# Jade_v1_schematics_PG2_ESP32_SUBSYS.net
KiCad netlist of a schematic drawn in Altium Designer
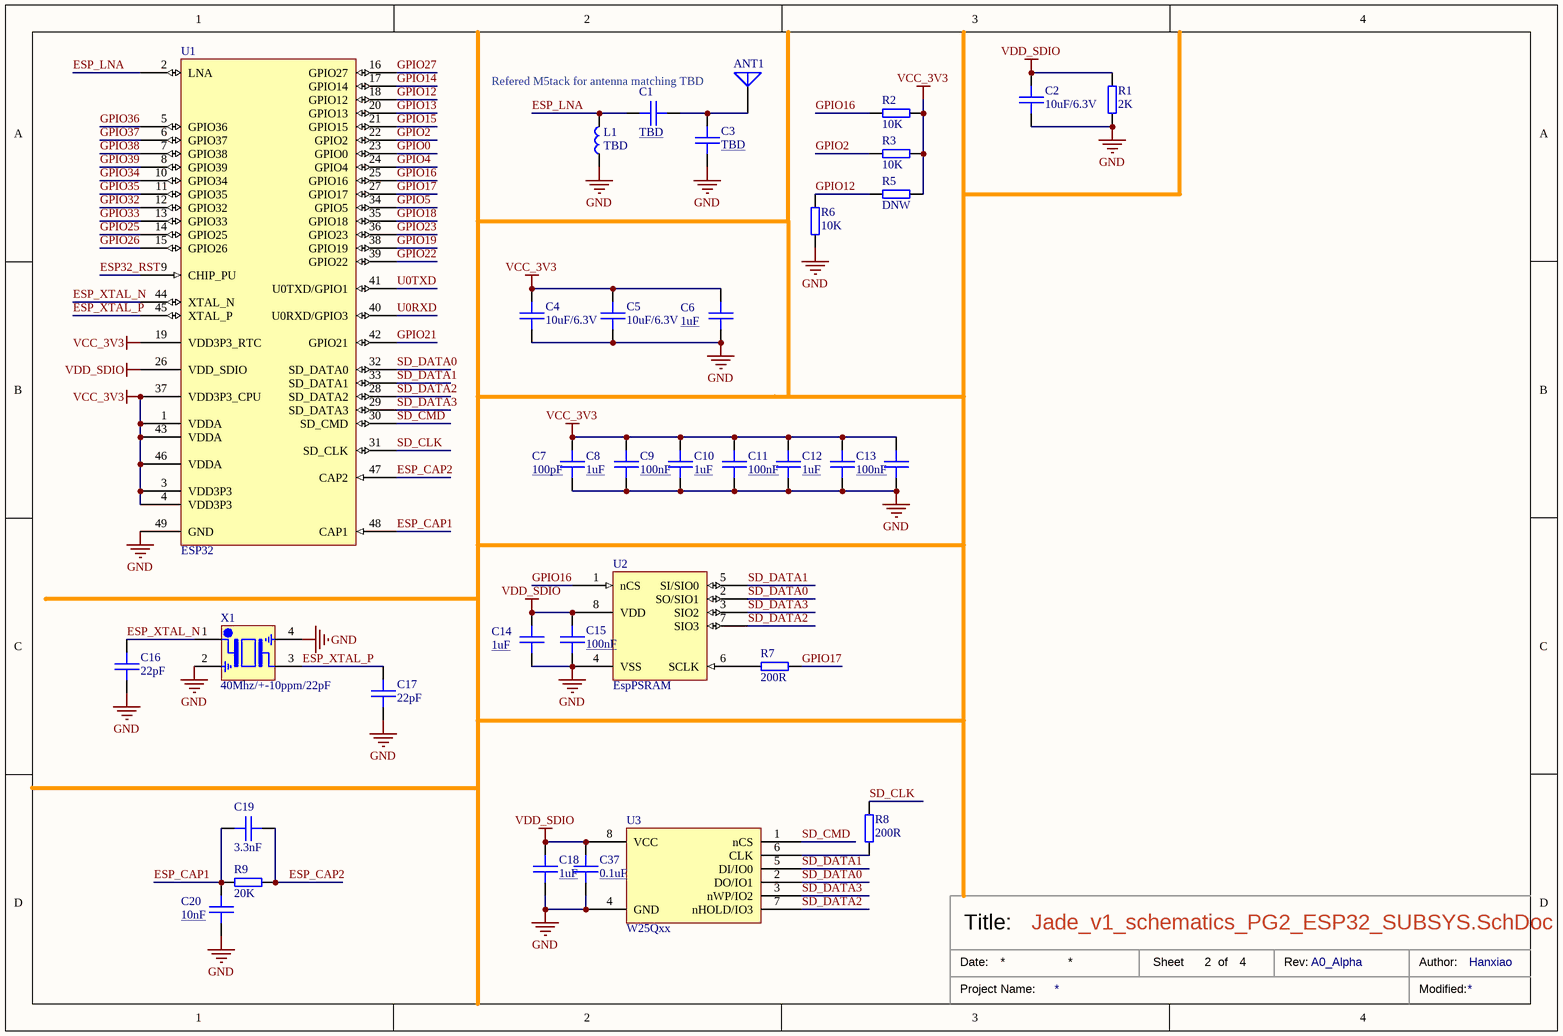
[diagram p0: Jade_v1_schematics_PG2_ESP32_SUBSYS.SchDoc]

(export (version "E")
  (design (tool "Eeschema 10.0.6"))
  (components
    (comp (ref "ANT1")
      (value "Antenna")
      (footprint "PRO-ANT-440")
      (description "Generic Antenna")
      (libsource (lib "Vowstar_Antenna") (part "Antenna"))
    )
    (comp (ref "C1")
      (value "TBD")
      (footprint "SMT_C_0402")
      (description "Surface mount capacitor 0402")
      (libsource (lib "Vowstar_Basic_Device") (part "SMT_C_0402"))
    )
    (comp (ref "C2")
      (value "10uF/6.3V")
      (footprint "SMT_C_0603")
      (description "Surface mount capacitor 0603")
      (libsource (lib "Vowstar_Basic_Device") (part "SMT_C_0603"))
    )
    (comp (ref "C3")
      (value "TBD")
      (footprint "SMT_C_0402")
      (description "Surface mount capacitor 0402")
      (libsource (lib "Vowstar_Basic_Device") (part "SMT_C_0402"))
    )
    (comp (ref "C4")
      (value "10uF/6.3V")
      (footprint "SMT_C_0603")
      (description "Surface mount capacitor 0603")
      (libsource (lib "Vowstar_Basic_Device") (part "SMT_C_0603"))
    )
    (comp (ref "C5")
      (value "10uF/6.3V")
      (footprint "SMT_C_0603")
      (description "Surface mount capacitor 0603")
      (libsource (lib "Vowstar_Basic_Device") (part "SMT_C_0603"))
    )
    (comp (ref "C6")
      (value "1uF")
      (footprint "SMT_C_0402")
      (description "Surface mount capacitor 0402")
      (libsource (lib "Vowstar_Basic_Device") (part "SMT_C_0402"))
    )
    (comp (ref "C7")
      (value "100pF")
      (footprint "SMT_C_0402")
      (description "Surface mount capacitor 0402")
      (libsource (lib "Vowstar_Basic_Device") (part "SMT_C_0402"))
    )
    (comp (ref "C8")
      (value "1uF")
      (footprint "SMT_C_0402")
      (description "Surface mount capacitor 0402")
      (libsource (lib "Vowstar_Basic_Device") (part "SMT_C_0402"))
    )
    (comp (ref "C9")
      (value "100nF")
      (footprint "SMT_C_0402")
      (description "Surface mount capacitor 0402")
      (libsource (lib "Vowstar_Basic_Device") (part "SMT_C_0402"))
    )
    (comp (ref "C10")
      (value "1uF")
      (footprint "SMT_C_0402")
      (description "Surface mount capacitor 0402")
      (libsource (lib "Vowstar_Basic_Device") (part "SMT_C_0402"))
    )
    (comp (ref "C11")
      (value "100nF")
      (footprint "SMT_C_0402")
      (description "Surface mount capacitor 0402")
      (libsource (lib "Vowstar_Basic_Device") (part "SMT_C_0402"))
    )
    (comp (ref "C12")
      (value "1uF")
      (footprint "SMT_C_0402")
      (description "Surface mount capacitor 0402")
      (libsource (lib "Vowstar_Basic_Device") (part "SMT_C_0402"))
    )
    (comp (ref "C13")
      (value "100nF")
      (footprint "SMT_C_0402")
      (description "Surface mount capacitor 0402")
      (libsource (lib "Vowstar_Basic_Device") (part "SMT_C_0402"))
    )
    (comp (ref "C14")
      (value "1uF")
      (footprint "SMT_C_0402")
      (description "Surface mount capacitor 0402")
      (libsource (lib "Vowstar_Basic_Device") (part "SMT_C_0402"))
    )
    (comp (ref "C15")
      (value "100nF")
      (footprint "SMT_C_0402")
      (description "Surface mount capacitor 0402")
      (libsource (lib "Vowstar_Basic_Device") (part "SMT_C_0402"))
    )
    (comp (ref "C16")
      (value "22pF")
      (footprint "SMT_C_0402")
      (description "Surface mount capacitor 0402")
      (libsource (lib "Vowstar_Basic_Device") (part "SMT_C_0402"))
    )
    (comp (ref "C17")
      (value "22pF")
      (footprint "SMT_C_0402")
      (description "Surface mount capacitor 0402")
      (libsource (lib "Vowstar_Basic_Device") (part "SMT_C_0402"))
    )
    (comp (ref "C18")
      (value "1uF")
      (footprint "SMT_C_0402")
      (description "Surface mount capacitor 0402")
      (libsource (lib "Vowstar_Basic_Device") (part "SMT_C_0402"))
    )
    (comp (ref "C19")
      (value "3.3nF")
      (footprint "SMT_C_0402")
      (description "Surface mount capacitor 0402")
      (libsource (lib "Vowstar_Basic_Device") (part "SMT_C_0402"))
    )
    (comp (ref "C20")
      (value "10nF")
      (footprint "SMT_C_0402")
      (description "Surface mount capacitor 0402")
      (libsource (lib "Vowstar_Basic_Device") (part "SMT_C_0402"))
    )
    (comp (ref "C37")
      (value "0.1uF")
      (footprint "SMT_C_0402")
      (description "Surface mount capacitor 0402")
      (libsource (lib "Vowstar_Basic_Device") (part "SMT_C_0402"))
    )
    (comp (ref "L1")
      (value "TBD")
      (footprint "SMT_L_0402")
      (description "Surface mount inductor 0402")
      (libsource (lib "Vowstar_Basic_Device") (part "SMT_L_0402"))
    )
    (comp (ref "R1")
      (value "2K")
      (footprint "SMT_R_0402")
      (description "Surface mount resistor 0402")
      (libsource (lib "Vowstar_Basic_Device") (part "SMT_R_0402"))
    )
    (comp (ref "R2")
      (value "10K")
      (footprint "SMT_R_0402")
      (description "Surface mount resistor 0402")
      (libsource (lib "Vowstar_Basic_Device") (part "SMT_R_0402"))
    )
    (comp (ref "R3")
      (value "10K")
      (footprint "SMT_R_0402")
      (description "Surface mount resistor 0402")
      (libsource (lib "Vowstar_Basic_Device") (part "SMT_R_0402"))
    )
    (comp (ref "R5")
      (value "DNW")
      (footprint "SMT_R_0402")
      (description "Surface mount resistor 0402")
      (libsource (lib "Vowstar_Basic_Device") (part "SMT_R_0402"))
    )
    (comp (ref "R6")
      (value "10K")
      (footprint "SMT_R_0402")
      (description "Surface mount resistor 0402")
      (libsource (lib "Vowstar_Basic_Device") (part "SMT_R_0402"))
    )
    (comp (ref "R7")
      (value "200R")
      (footprint "SMT_R_0402")
      (description "Surface mount resistor 0402")
      (libsource (lib "Vowstar_Basic_Device") (part "SMT_R_0402"))
    )
    (comp (ref "R8")
      (value "200R")
      (footprint "SMT_R_0402")
      (description "Surface mount resistor 0402")
      (libsource (lib "Vowstar_Basic_Device") (part "SMT_R_0402"))
    )
    (comp (ref "R9")
      (value "20K")
      (footprint "SMT_R_0402")
      (description "Surface mount resistor 0402")
      (libsource (lib "Vowstar_Basic_Device") (part "SMT_R_0402"))
    )
    (comp (ref "U1")
      (value "ESP32")
      (footprint "PQFN40P600X600X90_HS-49N")
      (libsource (lib "Espressif-CHIP") (part "ESP32"))
    )
    (comp (ref "U2") (value "EspPSRAM") (footprint "SOP-8") (libsource (lib "GENERAL-IC") (part "EspPSRAM")))
    (comp (ref "U3")
      (value "W25Qxx")
      (footprint "WSOP-8")
      (description "Serial flash memory with dual and quad SPI")
      (libsource (lib "Vowstar_IC_General") (part "W25QXX"))
    )
    (comp (ref "X1")
      (value "40Mhz/+-10ppm/22pF")
      (footprint "SMT_XTAL_2520")
      (description "Passive crystal")
      (libsource (lib "Vowstar_Basic_Device") (part "SMT_XTAL_PASSIVE"))
    )
  )
  (nets
    (net (code "1") (name "/ESP32_RST") (class "Default")
      (node (ref "U1") (pin "9") (pinfunction "CHIP_PU_9") (pintype "input"))
    )
    (net (code "2") (name "/ESP_CAP1") (class "Default")
      (node (ref "C19") (pin "1") (pinfunction "1_1") (pintype "passive"))
      (node (ref "C20") (pin "2") (pinfunction "2_2") (pintype "passive"))
      (node (ref "R9") (pin "1") (pinfunction "1_1") (pintype "passive"))
      (node (ref "U1") (pin "48") (pinfunction "CAP1_48") (pintype "input"))
    )
    (net (code "3") (name "/ESP_CAP2") (class "Default")
      (node (ref "C19") (pin "2") (pinfunction "2_2") (pintype "passive"))
      (node (ref "R9") (pin "2") (pinfunction "2_2") (pintype "passive"))
      (node (ref "U1") (pin "47") (pinfunction "CAP2_47") (pintype "input"))
    )
    (net (code "4") (name "/ESP_LNA") (class "Default")
      (node (ref "C1") (pin "1") (pinfunction "1_1") (pintype "passive"))
      (node (ref "L1") (pin "1") (pinfunction "1_1") (pintype "passive"))
      (node (ref "U1") (pin "2") (pinfunction "LNA_2") (pintype "bidirectional"))
    )
    (net (code "5") (name "/ESP_XTAL_N") (class "Default")
      (node (ref "C16") (pin "1") (pinfunction "1_1") (pintype "passive"))
      (node (ref "U1") (pin "44") (pinfunction "XTAL_N_44") (pintype "bidirectional"))
      (node (ref "X1") (pin "1") (pinfunction "IN/OUT_1") (pintype "passive"))
    )
    (net (code "6") (name "/ESP_XTAL_P") (class "Default")
      (node (ref "C17") (pin "1") (pinfunction "1_1") (pintype "passive"))
      (node (ref "U1") (pin "45") (pinfunction "XTAL_P_45") (pintype "bidirectional"))
      (node (ref "X1") (pin "3") (pinfunction "IN/OUT_3") (pintype "passive"))
    )
    (net (code "7") (name "/GPIO0") (class "Default")
      (node (ref "U1") (pin "23") (pinfunction "GPIO0_23") (pintype "bidirectional"))
    )
    (net (code "8") (name "/GPIO2") (class "Default")
      (node (ref "R3") (pin "1") (pinfunction "1_1") (pintype "passive"))
      (node (ref "U1") (pin "22") (pinfunction "GPIO2_22") (pintype "bidirectional"))
    )
    (net (code "9") (name "/GPIO4") (class "Default")
      (node (ref "U1") (pin "24") (pinfunction "GPIO4_24") (pintype "bidirectional"))
    )
    (net (code "10") (name "/GPIO5") (class "Default")
      (node (ref "U1") (pin "34") (pinfunction "GPIO5_34") (pintype "bidirectional"))
    )
    (net (code "11") (name "/GPIO12") (class "Default")
      (node (ref "R5") (pin "1") (pinfunction "1_1") (pintype "passive"))
      (node (ref "R6") (pin "2") (pinfunction "2_2") (pintype "passive"))
      (node (ref "U1") (pin "18") (pinfunction "GPIO12_18") (pintype "bidirectional"))
    )
    (net (code "12") (name "/GPIO13") (class "Default")
      (node (ref "U1") (pin "20") (pinfunction "GPIO13_20") (pintype "bidirectional"))
    )
    (net (code "13") (name "/GPIO14") (class "Default")
      (node (ref "U1") (pin "17") (pinfunction "GPIO14_17") (pintype "bidirectional"))
    )
    (net (code "14") (name "/GPIO15") (class "Default")
      (node (ref "U1") (pin "21") (pinfunction "GPIO15_21") (pintype "bidirectional"))
    )
    (net (code "15") (name "/GPIO16") (class "Default")
      (node (ref "R2") (pin "1") (pinfunction "1_1") (pintype "passive"))
      (node (ref "U1") (pin "25") (pinfunction "GPIO16_25") (pintype "bidirectional"))
      (node (ref "U2") (pin "1") (pinfunction "nCS_1") (pintype "input"))
    )
    (net (code "16") (name "/GPIO17") (class "Default")
      (node (ref "R7") (pin "1") (pinfunction "1_1") (pintype "passive"))
      (node (ref "U1") (pin "27") (pinfunction "GPIO17_27") (pintype "bidirectional"))
    )
    (net (code "17") (name "/GPIO18") (class "Default")
      (node (ref "U1") (pin "35") (pinfunction "GPIO18_35") (pintype "bidirectional"))
    )
    (net (code "18") (name "/GPIO19") (class "Default")
      (node (ref "U1") (pin "38") (pinfunction "GPIO19_38") (pintype "bidirectional"))
    )
    (net (code "19") (name "/GPIO21") (class "Default")
      (node (ref "U1") (pin "42") (pinfunction "GPIO21_42") (pintype "bidirectional"))
    )
    (net (code "20") (name "/GPIO22") (class "Default")
      (node (ref "U1") (pin "39") (pinfunction "GPIO22_39") (pintype "bidirectional"))
    )
    (net (code "21") (name "/GPIO23") (class "Default")
      (node (ref "U1") (pin "36") (pinfunction "GPIO23_36") (pintype "bidirectional"))
    )
    (net (code "22") (name "/GPIO25") (class "Default")
      (node (ref "U1") (pin "14") (pinfunction "GPIO25_14") (pintype "bidirectional"))
    )
    (net (code "23") (name "/GPIO26") (class "Default")
      (node (ref "U1") (pin "15") (pinfunction "GPIO26_15") (pintype "bidirectional"))
    )
    (net (code "24") (name "/GPIO27") (class "Default")
      (node (ref "U1") (pin "16") (pinfunction "GPIO27_16") (pintype "bidirectional"))
    )
    (net (code "25") (name "/GPIO32") (class "Default")
      (node (ref "U1") (pin "12") (pinfunction "GPIO32_12") (pintype "bidirectional"))
    )
    (net (code "26") (name "/GPIO33") (class "Default")
      (node (ref "U1") (pin "13") (pinfunction "GPIO33_13") (pintype "bidirectional"))
    )
    (net (code "27") (name "/GPIO34") (class "Default")
      (node (ref "U1") (pin "10") (pinfunction "GPIO34_10") (pintype "bidirectional"))
    )
    (net (code "28") (name "/GPIO35") (class "Default")
      (node (ref "U1") (pin "11") (pinfunction "GPIO35_11") (pintype "bidirectional"))
    )
    (net (code "29") (name "/GPIO36") (class "Default")
      (node (ref "U1") (pin "5") (pinfunction "GPIO36_5") (pintype "bidirectional"))
    )
    (net (code "30") (name "/GPIO37") (class "Default")
      (node (ref "U1") (pin "6") (pinfunction "GPIO37_6") (pintype "bidirectional"))
    )
    (net (code "31") (name "/GPIO38") (class "Default")
      (node (ref "U1") (pin "7") (pinfunction "GPIO38_7") (pintype "bidirectional"))
    )
    (net (code "32") (name "/GPIO39") (class "Default")
      (node (ref "U1") (pin "8") (pinfunction "GPIO39_8") (pintype "bidirectional"))
    )
    (net (code "33") (name "/SD_CLK") (class "Default")
      (node (ref "R8") (pin "1") (pinfunction "1_1") (pintype "passive"))
      (node (ref "U1") (pin "31") (pinfunction "SD_CLK_31") (pintype "bidirectional"))
    )
    (net (code "34") (name "/SD_CMD") (class "Default")
      (node (ref "U1") (pin "30") (pinfunction "SD_CMD_30") (pintype "bidirectional"))
      (node (ref "U3") (pin "1") (pinfunction "nCS_1") (pintype "passive"))
    )
    (net (code "35") (name "/SD_DATA0") (class "Default")
      (node (ref "U1") (pin "32") (pinfunction "SD_DATA0_32") (pintype "bidirectional"))
      (node (ref "U2") (pin "2") (pinfunction "SO/SIO1_2") (pintype "bidirectional"))
      (node (ref "U3") (pin "2") (pinfunction "DO/IO1_2") (pintype "passive"))
    )
    (net (code "36") (name "/SD_DATA1") (class "Default")
      (node (ref "U1") (pin "33") (pinfunction "SD_DATA1_33") (pintype "bidirectional"))
      (node (ref "U2") (pin "5") (pinfunction "SI/SIO0_5") (pintype "bidirectional"))
      (node (ref "U3") (pin "5") (pinfunction "DI/IO0_5") (pintype "passive"))
    )
    (net (code "37") (name "/SD_DATA2") (class "Default")
      (node (ref "U1") (pin "28") (pinfunction "SD_DATA2_28") (pintype "bidirectional"))
      (node (ref "U2") (pin "7") (pinfunction "SIO3_7") (pintype "bidirectional"))
      (node (ref "U3") (pin "7") (pinfunction "nHOLD/IO3_7") (pintype "passive"))
    )
    (net (code "38") (name "/SD_DATA3") (class "Default")
      (node (ref "U1") (pin "29") (pinfunction "SD_DATA3_29") (pintype "bidirectional"))
      (node (ref "U2") (pin "3") (pinfunction "SIO2_3") (pintype "bidirectional"))
      (node (ref "U3") (pin "3") (pinfunction "nWP/IO2_3") (pintype "passive"))
    )
    (net (code "39") (name "/U0RXD") (class "Default")
      (node (ref "U1") (pin "40") (pinfunction "U0RXD/GPIO3_40") (pintype "bidirectional"))
    )
    (net (code "40") (name "/U0TXD") (class "Default")
      (node (ref "U1") (pin "41") (pinfunction "U0TXD/GPIO1_41") (pintype "bidirectional"))
    )
    (net (code "41") (name "GND") (class "Default")
      (node (ref "C10") (pin "1") (pinfunction "1_1") (pintype "passive"))
      (node (ref "C11") (pin "1") (pinfunction "1_1") (pintype "passive"))
      (node (ref "C12") (pin "1") (pinfunction "1_1") (pintype "passive"))
      (node (ref "C13") (pin "1") (pinfunction "1_1") (pintype "passive"))
      (node (ref "C14") (pin "1") (pinfunction "1_1") (pintype "passive"))
      (node (ref "C15") (pin "1") (pinfunction "1_1") (pintype "passive"))
      (node (ref "C16") (pin "2") (pinfunction "2_2") (pintype "passive"))
      (node (ref "C17") (pin "2") (pinfunction "2_2") (pintype "passive"))
      (node (ref "C18") (pin "2") (pinfunction "2_2") (pintype "passive"))
      (node (ref "C2") (pin "2") (pinfunction "2_2") (pintype "passive"))
      (node (ref "C20") (pin "1") (pinfunction "1_1") (pintype "passive"))
      (node (ref "C3") (pin "1") (pinfunction "1_1") (pintype "passive"))
      (node (ref "C37") (pin "1") (pinfunction "1_1") (pintype "passive"))
      (node (ref "C4") (pin "2") (pinfunction "2_2") (pintype "passive"))
      (node (ref "C5") (pin "2") (pinfunction "2_2") (pintype "passive"))
      (node (ref "C6") (pin "1") (pinfunction "1_1") (pintype "passive"))
      (node (ref "C7") (pin "1") (pinfunction "1_1") (pintype "passive"))
      (node (ref "C8") (pin "1") (pinfunction "1_1") (pintype "passive"))
      (node (ref "C9") (pin "1") (pinfunction "1_1") (pintype "passive"))
      (node (ref "L1") (pin "2") (pinfunction "2_2") (pintype "passive"))
      (node (ref "R1") (pin "1") (pinfunction "1_1") (pintype "passive"))
      (node (ref "R6") (pin "1") (pinfunction "1_1") (pintype "passive"))
      (node (ref "U1") (pin "49") (pinfunction "GND_49") (pintype "power_in"))
      (node (ref "U2") (pin "4") (pinfunction "VSS_4") (pintype "power_in"))
      (node (ref "U3") (pin "4") (pinfunction "GND_4") (pintype "passive"))
      (node (ref "X1") (pin "2") (pinfunction "GND_2") (pintype "passive"))
      (node (ref "X1") (pin "4") (pinfunction "GND_4") (pintype "passive"))
    )
    (net (code "42") (name "Net-(ANT1-A)") (class "Default")
      (node (ref "ANT1") (pin "1") (pinfunction "A_1") (pintype "passive"))
      (node (ref "C1") (pin "2") (pinfunction "2_2") (pintype "passive"))
      (node (ref "C3") (pin "2") (pinfunction "2_2") (pintype "passive"))
    )
    (net (code "43") (name "Net-(U2-SCLK)") (class "Default")
      (node (ref "R7") (pin "2") (pinfunction "2_2") (pintype "passive"))
      (node (ref "U2") (pin "6") (pinfunction "SCLK_6") (pintype "input"))
    )
    (net (code "44") (name "Net-(U3-CLK)") (class "Default")
      (node (ref "R8") (pin "2") (pinfunction "2_2") (pintype "passive"))
      (node (ref "U3") (pin "6") (pinfunction "CLK_6") (pintype "passive"))
    )
    (net (code "45") (name "VCC_3V3") (class "Default")
      (node (ref "C10") (pin "2") (pinfunction "2_2") (pintype "passive"))
      (node (ref "C11") (pin "2") (pinfunction "2_2") (pintype "passive"))
      (node (ref "C12") (pin "2") (pinfunction "2_2") (pintype "passive"))
      (node (ref "C13") (pin "2") (pinfunction "2_2") (pintype "passive"))
      (node (ref "C4") (pin "1") (pinfunction "1_1") (pintype "passive"))
      (node (ref "C5") (pin "1") (pinfunction "1_1") (pintype "passive"))
      (node (ref "C6") (pin "2") (pinfunction "2_2") (pintype "passive"))
      (node (ref "C7") (pin "2") (pinfunction "2_2") (pintype "passive"))
      (node (ref "C8") (pin "2") (pinfunction "2_2") (pintype "passive"))
      (node (ref "C9") (pin "2") (pinfunction "2_2") (pintype "passive"))
      (node (ref "R2") (pin "2") (pinfunction "2_2") (pintype "passive"))
      (node (ref "R3") (pin "2") (pinfunction "2_2") (pintype "passive"))
      (node (ref "R5") (pin "2") (pinfunction "2_2") (pintype "passive"))
      (node (ref "U1") (pin "1") (pinfunction "VDDA_1") (pintype "power_in"))
      (node (ref "U1") (pin "19") (pinfunction "VDD3P3_RTC_19") (pintype "power_in"))
      (node (ref "U1") (pin "3") (pinfunction "VDD3P3_3") (pintype "power_in"))
      (node (ref "U1") (pin "37") (pinfunction "VDD3P3_CPU_37") (pintype "power_in"))
      (node (ref "U1") (pin "4") (pinfunction "VDD3P3_4") (pintype "power_in"))
      (node (ref "U1") (pin "43") (pinfunction "VDDA_43") (pintype "power_in"))
      (node (ref "U1") (pin "46") (pinfunction "VDDA_46") (pintype "power_in"))
    )
    (net (code "46") (name "VDD_SDIO") (class "Default")
      (node (ref "C14") (pin "2") (pinfunction "2_2") (pintype "passive"))
      (node (ref "C15") (pin "2") (pinfunction "2_2") (pintype "passive"))
      (node (ref "C18") (pin "1") (pinfunction "1_1") (pintype "passive"))
      (node (ref "C2") (pin "1") (pinfunction "1_1") (pintype "passive"))
      (node (ref "C37") (pin "2") (pinfunction "2_2") (pintype "passive"))
      (node (ref "R1") (pin "2") (pinfunction "2_2") (pintype "passive"))
      (node (ref "U1") (pin "26") (pinfunction "VDD_SDIO_26") (pintype "power_in"))
      (node (ref "U2") (pin "8") (pinfunction "VDD_8") (pintype "power_in"))
      (node (ref "U3") (pin "8") (pinfunction "VCC_8") (pintype "passive"))
    )
  )
)
